# DetectionSch.net
KiCad netlist of a schematic drawn in Altium Designer
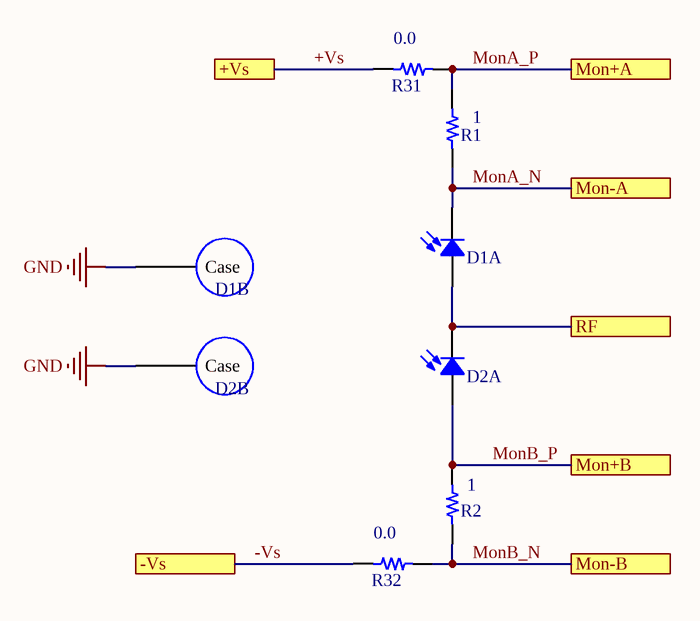
[diagram p0: DetectionSch.SchDoc]

(export (version "E")
  (design (tool "Eeschema 10.0.6"))
  (components
    (comp (ref "D1")
      (value "S5973-02")
      (footprint "TO-18")
      (description "The S5973-02 is a high-speed Si PIN photodiode des")
      (fields (field (name "MANUFACTURER") "Hamamatsu"))
      (libsource (lib "") (part "Photodiode 3Pin_1"))
    )
    (comp (ref "D2")
      (value "S5973-02")
      (footprint "TO-18")
      (description "The S5973-02 is a high-speed Si PIN photodiode des")
      (fields (field (name "MANUFACTURER") "Hamamatsu"))
      (libsource (lib "Celestial Library Database") (part "Photodiode 3Pin"))
    )
    (comp (ref "R1")
      (value "1")
      (footprint "STACKPOLE CSR1206")
      (description "RES SMD 1 OHM 1% 1/2W 1206")
      (fields
        (field (name "PART NUMBER") "CSR1206FK1R00")
        (field (name "MANUFACTURER") "Stackpole Electronics Inc.")
      )
      (libsource (lib "Celestial Library Database") (part "Resistor"))
    )
    (comp (ref "R2")
      (value "1")
      (footprint "STACKPOLE CSR1206")
      (description "RES SMD 1 OHM 1% 1/2W 1206")
      (fields
        (field (name "PART NUMBER") "CSR1206FK1R00")
        (field (name "MANUFACTURER") "Stackpole Electronics Inc.")
      )
      (libsource (lib "Celestial Library Database") (part "Resistor"))
    )
    (comp (ref "R31")
      (value "0.0")
      (footprint "RES 0402/1005")
      (description "RES SMD 0.0OHM JUMPER 1/10W 0402")
      (fields
        (field (name "PART NUMBER") "ERJ-2GE0R00X")
        (field (name "MANUFACTURER") "Panasonic Electronic Components")
      )
      (libsource (lib "Celestial Library Database") (part "Resistor"))
    )
    (comp (ref "R32")
      (value "0.0")
      (footprint "RES 0402/1005")
      (description "RES SMD 0.0OHM JUMPER 1/10W 0402")
      (fields
        (field (name "PART NUMBER") "ERJ-2GE0R00X")
        (field (name "MANUFACTURER") "Panasonic Electronic Components")
      )
      (libsource (lib "Celestial Library Database") (part "Resistor"))
    )
  )
  (nets
    (net (code "1") (name "/+Vs") (class "Default")
      (node (ref "R31") (pin "1") (pinfunction "1_1") (pintype "passive"))
    )
    (net (code "2") (name "/-Vs") (class "Default")
      (node (ref "R32") (pin "1") (pinfunction "1_1") (pintype "passive"))
    )
    (net (code "3") (name "/MonA_N") (class "Default")
      (node (ref "D1") (pin "1") (pinfunction "1_1") (pintype "passive"))
      (node (ref "R1") (pin "2") (pinfunction "2_2") (pintype "passive"))
    )
    (net (code "4") (name "/MonA_P") (class "Default")
      (node (ref "R1") (pin "1") (pinfunction "1_1") (pintype "passive"))
      (node (ref "R31") (pin "2") (pinfunction "2_2") (pintype "passive"))
    )
    (net (code "5") (name "/MonB_N") (class "Default")
      (node (ref "R2") (pin "1") (pinfunction "1_1") (pintype "passive"))
      (node (ref "R32") (pin "2") (pinfunction "2_2") (pintype "passive"))
    )
    (net (code "6") (name "/MonB_P") (class "Default")
      (node (ref "D2") (pin "3") (pinfunction "3_3") (pintype "passive"))
      (node (ref "R2") (pin "2") (pinfunction "2_2") (pintype "passive"))
    )
    (net (code "7") (name "/RF") (class "Default")
      (node (ref "D1") (pin "3") (pinfunction "3_3") (pintype "passive"))
      (node (ref "D2") (pin "1") (pinfunction "1_1") (pintype "passive"))
    )
    (net (code "8") (name "GND") (class "Default")
      (node (ref "D1") (pin "2") (pinfunction "Case_2") (pintype "passive"))
      (node (ref "D2") (pin "2") (pinfunction "Case_2") (pintype "passive"))
    )
  )
)
